# ModDS3231.net
KiCad netlist of a schematic drawn in Altium Designer
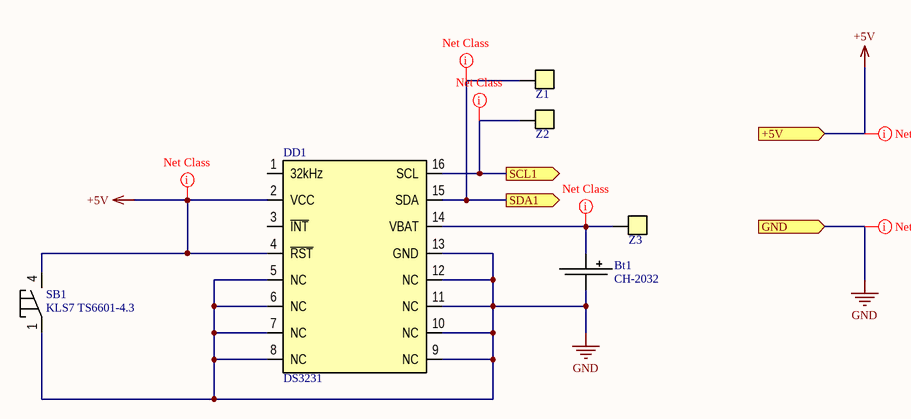
[diagram p0: ModDS3231.SchDoc]

(export (version "E")
  (design (tool "Eeschema 10.0.6"))
  (components
    (comp (ref "Bt1")
      (value "CH-2032")
      (footprint "CH25-2032")
      (fields (field (name "PART NUMBER") "CH25-2032") (field (name "MANUFACTURER") "Comf"))
      (libsource (lib "SchlibUGO") (part "CR-2032"))
    )
    (comp (ref "DD1")
      (value "DS3231")
      (footprint "SO-16")
      (fields (field (name "PART NUMBER") "DS3231SN"))
      (libsource (lib "SchlibUGO") (part "DS3231"))
    )
    (comp (ref "SB1")
      (value "KLS7 TS6601-4.3")
      (footprint "KLS2")
      (fields (field (name "MANUFACTURER") "KLS"))
      (libsource (lib "SchlibUGO") (part "Button"))
    )
    (comp (ref "Z1")
      (value "test Point")
      (footprint "test Point")
      (libsource (lib "SchlibUGO") (part "test Point"))
    )
    (comp (ref "Z2")
      (value "test Point")
      (footprint "test Point")
      (libsource (lib "SchlibUGO") (part "test Point"))
    )
    (comp (ref "Z3")
      (value "test Point")
      (footprint "test Point")
      (libsource (lib "SchlibUGO") (part "test Point"))
    )
  )
  (nets
    (net (code "1") (name "+5V") (class "Default")
      (node (ref "DD1") (pin "2") (pinfunction "VCC_2") (pintype "passive"))
      (node (ref "DD1") (pin "4") (pinfunction "~{RST}_4") (pintype "passive"))
      (node (ref "SB1") (pin "4") (pinfunction "4_4") (pintype "passive"))
    )
    (net (code "2") (name "/SCL1") (class "Default")
      (node (ref "DD1") (pin "16") (pinfunction "SCL_16") (pintype "passive"))
      (node (ref "Z2") (pin "1") (pinfunction "1_1") (pintype "passive"))
    )
    (net (code "3") (name "/SDA1") (class "Default")
      (node (ref "DD1") (pin "15") (pinfunction "SDA_15") (pintype "passive"))
      (node (ref "Z1") (pin "1") (pinfunction "1_1") (pintype "passive"))
    )
    (net (code "4") (name "GND") (class "Default")
      (node (ref "Bt1") (pin "2") (pinfunction "2_2") (pintype "passive"))
      (node (ref "DD1") (pin "10") (pinfunction "NC_10") (pintype "passive"))
      (node (ref "DD1") (pin "11") (pinfunction "NC_11") (pintype "passive"))
      (node (ref "DD1") (pin "12") (pinfunction "NC_12") (pintype "passive"))
      (node (ref "DD1") (pin "13") (pinfunction "GND_13") (pintype "passive"))
      (node (ref "DD1") (pin "5") (pinfunction "NC_5") (pintype "passive"))
      (node (ref "DD1") (pin "6") (pinfunction "NC_6") (pintype "passive"))
      (node (ref "DD1") (pin "7") (pinfunction "NC_7") (pintype "passive"))
      (node (ref "DD1") (pin "8") (pinfunction "NC_8") (pintype "passive"))
      (node (ref "DD1") (pin "9") (pinfunction "NC_9") (pintype "passive"))
      (node (ref "SB1") (pin "1") (pinfunction "1_1") (pintype "passive"))
    )
    (net (code "5") (name "Net-(DD1-VBAT)") (class "Default")
      (node (ref "Bt1") (pin "1") (pinfunction "1_1") (pintype "passive"))
      (node (ref "DD1") (pin "14") (pinfunction "VBAT_14") (pintype "passive"))
      (node (ref "Z3") (pin "1") (pinfunction "1_1") (pintype "passive"))
    )
    (net (code "6") (name "unconnected-(DD1-32kHz-Pad1)") (class "Default")
      (node (ref "DD1") (pin "1") (pinfunction "32kHz_1") (pintype "passive"))
    )
    (net (code "7") (name "unconnected-(DD1-~{INT}-Pad3)") (class "Default")
      (node (ref "DD1") (pin "3") (pinfunction "~{INT}_3") (pintype "passive"))
    )
  )
)
